# project_konovalov_motor_driver.net
KiCad netlist of a schematic drawn in Altium Designer
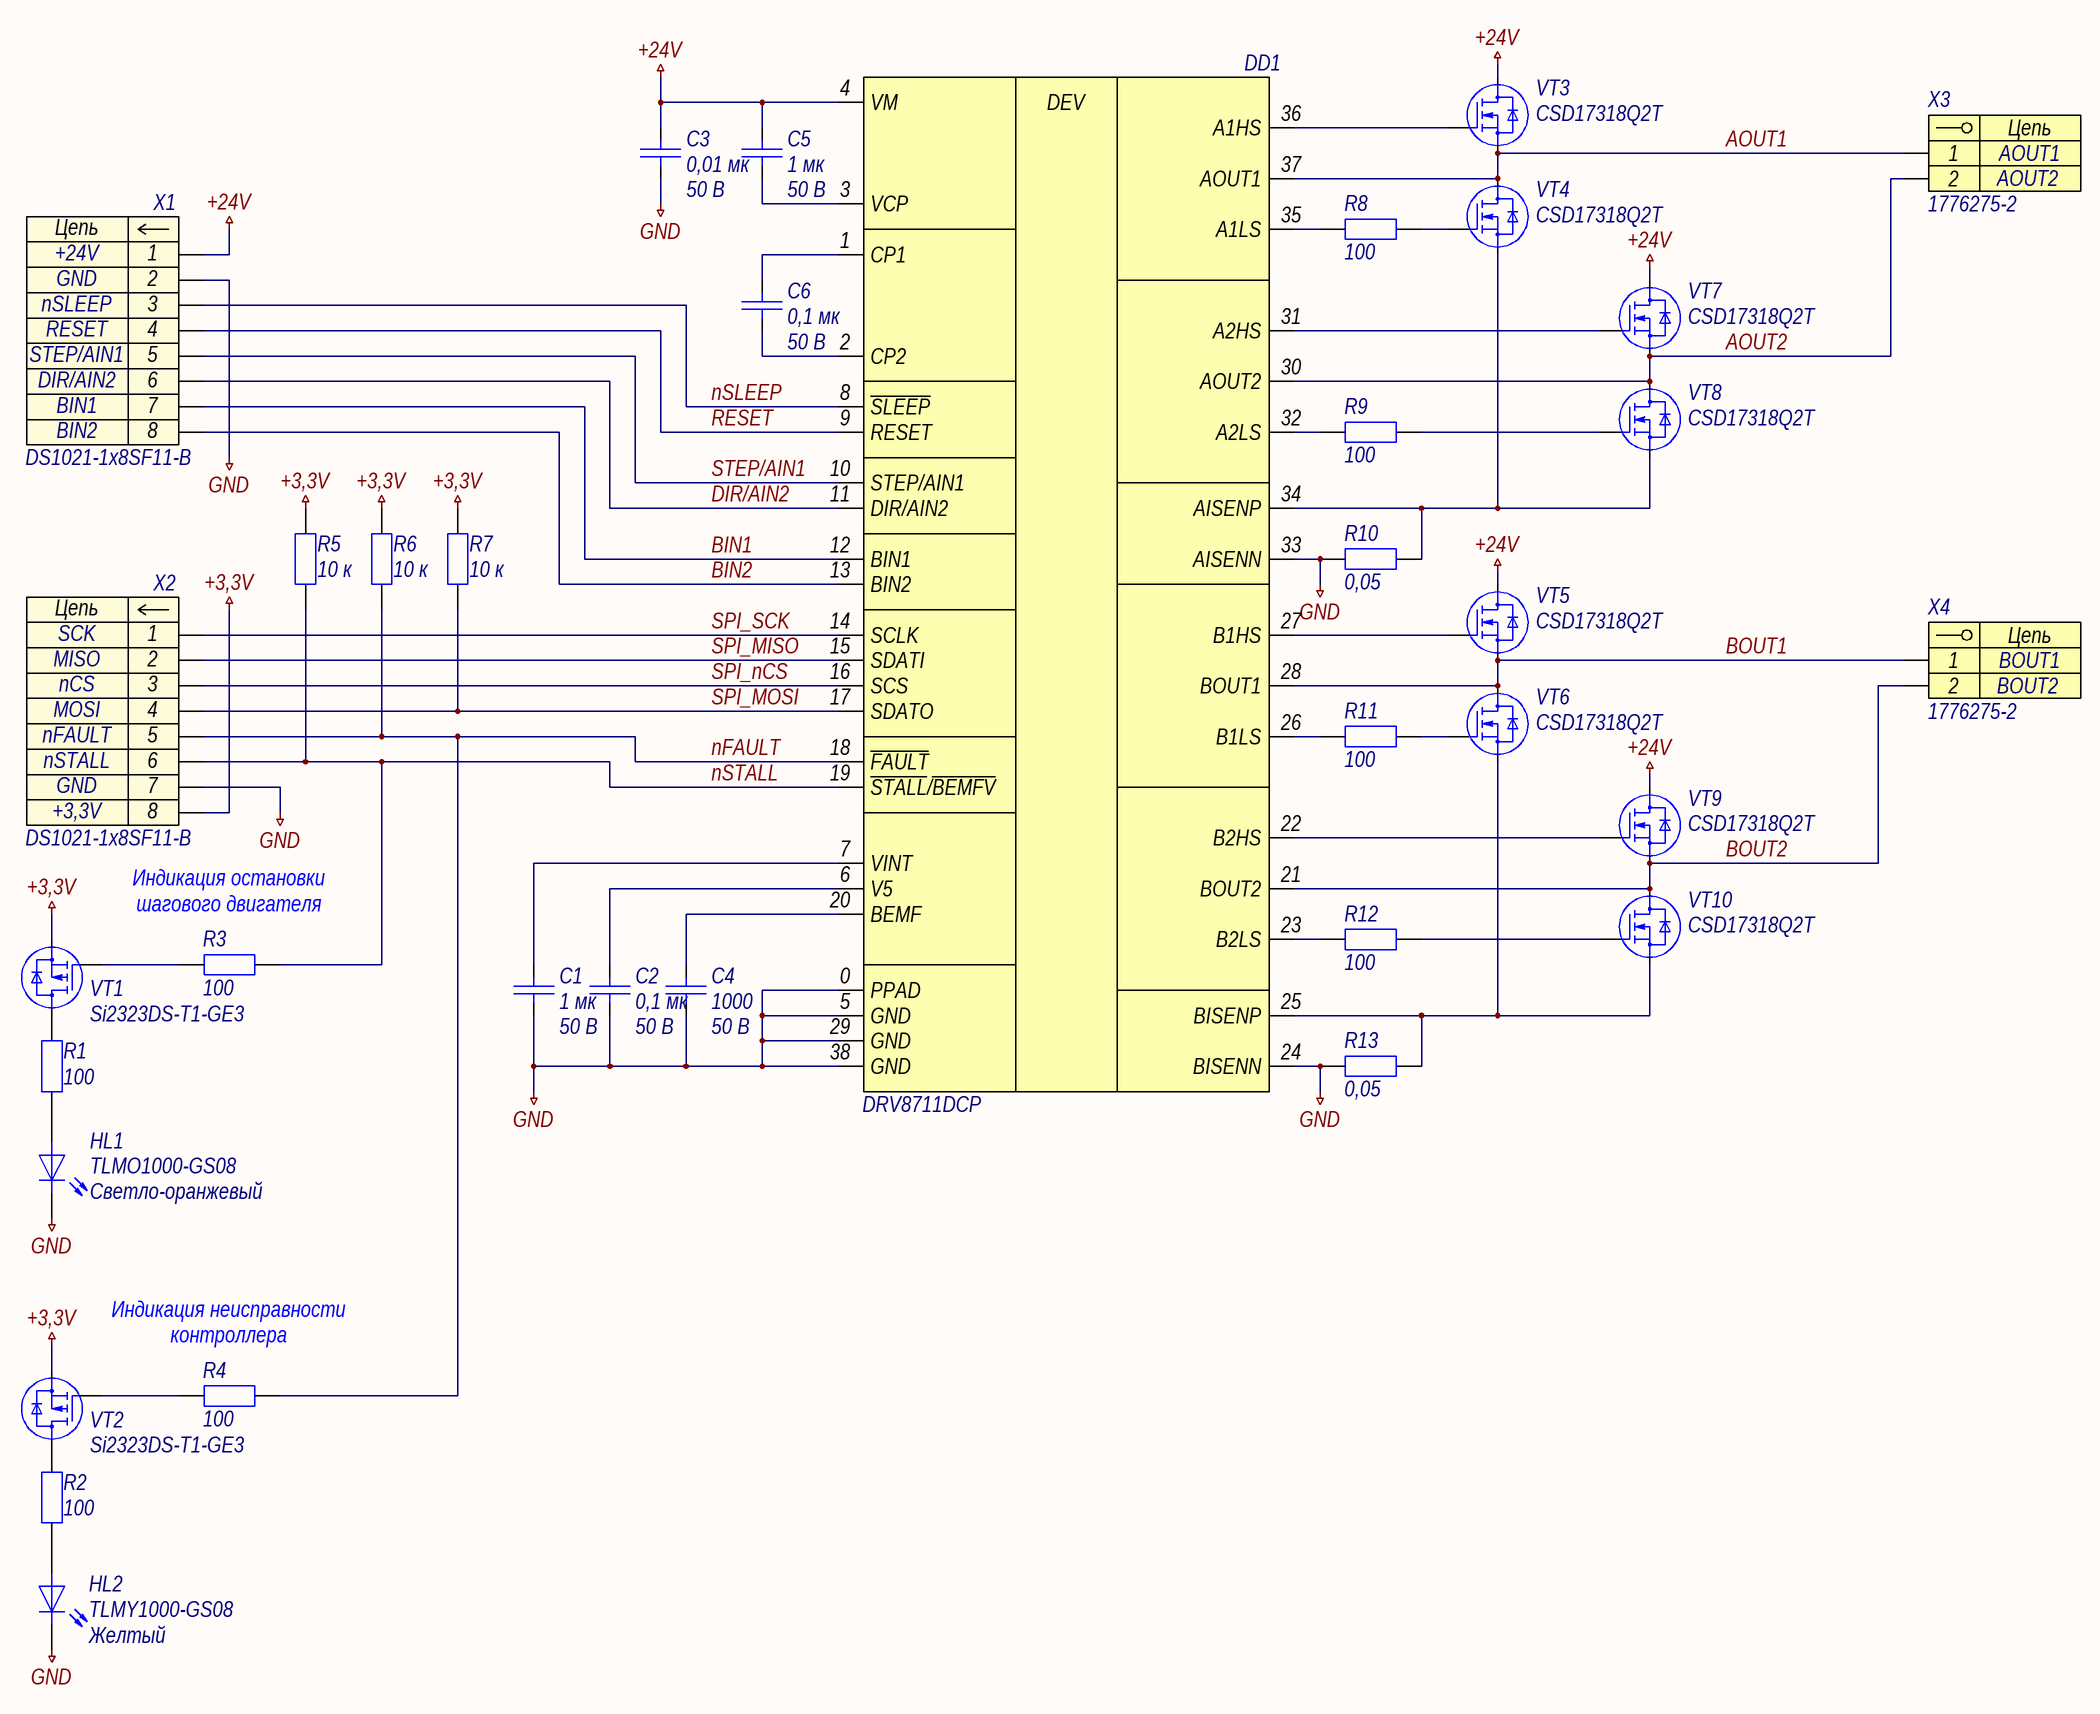
[diagram p0: project_konovalov_motor_driver.SchDoc]

(export (version "E")
  (design (tool "Eeschema 10.0.6"))
  (components
    (comp (ref "C1")
      (value "1 мк")
      (footprint "C0603")
      (description "=Описание")
      (fields (field (name "НАПРЯЖЕНИЕ") "50 В"))
      (libsource (lib "Database_Students") (part "CAPACITOR-NONPOLAR"))
    )
    (comp (ref "C2")
      (value "0,1 мк")
      (footprint "C0603")
      (description "=Описание")
      (fields (field (name "НАПРЯЖЕНИЕ") "50 В"))
      (libsource (lib "Database_Students") (part "CAPACITOR-NONPOLAR"))
    )
    (comp (ref "C3")
      (value "0,01 мк")
      (footprint "C0603")
      (description "=Описание")
      (fields (field (name "НАПРЯЖЕНИЕ") "50 В"))
      (libsource (lib "Database_Students") (part "CAPACITOR-NONPOLAR"))
    )
    (comp (ref "C4")
      (value "1000")
      (footprint "C0603")
      (description "=Описание")
      (fields (field (name "НАПРЯЖЕНИЕ") "50 В"))
      (libsource (lib "Database_Students") (part "CAPACITOR-NONPOLAR"))
    )
    (comp (ref "C5")
      (value "1 мк")
      (footprint "C0603")
      (description "=Описание")
      (fields (field (name "НАПРЯЖЕНИЕ") "50 В"))
      (libsource (lib "Database_Students") (part "CAPACITOR-NONPOLAR"))
    )
    (comp (ref "C6")
      (value "0,1 мк")
      (footprint "C0603")
      (description "=Описание")
      (fields (field (name "НАПРЯЖЕНИЕ") "50 В"))
      (libsource (lib "Database_Students") (part "CAPACITOR-NONPOLAR"))
    )
    (comp (ref "DD1")
      (value "DRV8711DCP")
      (footprint "HTSSOP-38-P50-470X290X120-L63X22-T470X290")
      (description "=Описание")
      (libsource (lib "Database_Students") (part "DRV8711DCP"))
    )
    (comp (ref "HL1")
      (value "TLMO1000-GS08")
      (footprint "HL0603")
      (description "=Описание")
      (fields (field (name "ЦВЕТ") "Светло-оранжевый"))
      (libsource (lib "Database_Students") (part "LED-COMMON"))
    )
    (comp (ref "HL2")
      (value "TLMY1000-GS08")
      (footprint "HL0603")
      (description "=Описание")
      (fields (field (name "ЦВЕТ") "Желтый"))
      (libsource (lib "Database_Students") (part "LED-COMMON"))
    )
    (comp (ref "R1")
      (value "100")
      (footprint "R0603")
      (description "=Описание")
      (libsource (lib "Database_Students") (part "RESISTOR-COMMON"))
    )
    (comp (ref "R2")
      (value "100")
      (footprint "R0603")
      (description "=Описание")
      (libsource (lib "Database_Students") (part "RESISTOR-COMMON"))
    )
    (comp (ref "R3")
      (value "100")
      (footprint "R0603")
      (description "=Описание")
      (libsource (lib "Database_Students") (part "RESISTOR-COMMON"))
    )
    (comp (ref "R4")
      (value "100")
      (footprint "R0603")
      (description "=Описание")
      (libsource (lib "Database_Students") (part "RESISTOR-COMMON"))
    )
    (comp (ref "R5")
      (value "10 к")
      (footprint "R0603")
      (description "=Описание")
      (libsource (lib "Database_Students") (part "RESISTOR-COMMON"))
    )
    (comp (ref "R6")
      (value "10 к")
      (footprint "R0603")
      (description "=Описание")
      (libsource (lib "Database_Students") (part "RESISTOR-COMMON"))
    )
    (comp (ref "R7")
      (value "10 к")
      (footprint "R0603")
      (description "=Описание")
      (libsource (lib "Database_Students") (part "RESISTOR-COMMON"))
    )
    (comp (ref "R8")
      (value "100")
      (footprint "R0603")
      (description "=Описание")
      (libsource (lib "Database_Students") (part "RESISTOR-COMMON"))
    )
    (comp (ref "R9")
      (value "100")
      (footprint "R0603")
      (description "=Описание")
      (libsource (lib "Database_Students") (part "RESISTOR-COMMON"))
    )
    (comp (ref "R10")
      (value "0,05")
      (footprint "R0603")
      (description "=Описание")
      (libsource (lib "Database_Students") (part "RESISTOR-COMMON"))
    )
    (comp (ref "R11")
      (value "100")
      (footprint "R0603")
      (description "=Описание")
      (libsource (lib "Database_Students") (part "RESISTOR-COMMON"))
    )
    (comp (ref "R12")
      (value "100")
      (footprint "R0603")
      (description "=Описание")
      (libsource (lib "Database_Students") (part "RESISTOR-COMMON"))
    )
    (comp (ref "R13")
      (value "0,05")
      (footprint "R0603")
      (description "=Описание")
      (libsource (lib "Database_Students") (part "RESISTOR-COMMON"))
    )
    (comp (ref "VT1")
      (value "Si2323DS-T1-GE3")
      (footprint "SOT-23-3-P95-292X237X112")
      (description "=Описание")
      (libsource (lib "Database_Students") (part "MOSFET-P-DIODE"))
    )
    (comp (ref "VT2")
      (value "Si2323DS-T1-GE3")
      (footprint "SOT-23-3-P95-292X237X112")
      (description "=Описание")
      (libsource (lib "Database_Students") (part "MOSFET-P-DIODE"))
    )
    (comp (ref "VT3")
      (value "CSD17318Q2T")
      (footprint "WSON-6-P65-200X200X80")
      (description "=Описание")
      (libsource (lib "Database_Students") (part "MOSFET-N-DIODE"))
    )
    (comp (ref "VT4")
      (value "CSD17318Q2T")
      (footprint "WSON-6-P65-200X200X80")
      (description "=Описание")
      (libsource (lib "Database_Students") (part "MOSFET-N-DIODE"))
    )
    (comp (ref "VT5")
      (value "CSD17318Q2T")
      (footprint "WSON-6-P65-200X200X80")
      (description "=Описание")
      (libsource (lib "Database_Students") (part "MOSFET-N-DIODE"))
    )
    (comp (ref "VT6")
      (value "CSD17318Q2T")
      (footprint "WSON-6-P65-200X200X80")
      (description "=Описание")
      (libsource (lib "Database_Students") (part "MOSFET-N-DIODE"))
    )
    (comp (ref "VT7")
      (value "CSD17318Q2T")
      (footprint "WSON-6-P65-200X200X80")
      (description "=Описание")
      (libsource (lib "Database_Students") (part "MOSFET-N-DIODE"))
    )
    (comp (ref "VT8")
      (value "CSD17318Q2T")
      (footprint "WSON-6-P65-200X200X80")
      (description "=Описание")
      (libsource (lib "Database_Students") (part "MOSFET-N-DIODE"))
    )
    (comp (ref "VT9")
      (value "CSD17318Q2T")
      (footprint "WSON-6-P65-200X200X80")
      (description "=Описание")
      (libsource (lib "Database_Students") (part "MOSFET-N-DIODE"))
    )
    (comp (ref "VT10")
      (value "CSD17318Q2T")
      (footprint "WSON-6-P65-200X200X80")
      (description "=Описание")
      (libsource (lib "Database_Students") (part "MOSFET-N-DIODE"))
    )
    (comp (ref "X1")
      (value "DS1021-1x8SF11-B")
      (footprint "DS1021-1X8SF11-B")
      (description "=Описание")
      (libsource (lib "Database_Students") (part "HEADER-8-PLG"))
    )
    (comp (ref "X2")
      (value "DS1021-1x8SF11-B")
      (footprint "DS1021-1X8SF11-B")
      (description "=Описание")
      (libsource (lib "Database_Students") (part "HEADER-8-PLG"))
    )
    (comp (ref "X3")
      (value "1776275-2")
      (footprint "1776275-2")
      (description "=Описание")
      (libsource (lib "Database_Students") (part "HEADER-2-TRM"))
    )
    (comp (ref "X4")
      (value "1776275-2")
      (footprint "1776275-2")
      (description "=Описание")
      (libsource (lib "Database_Students") (part "HEADER-2-TRM"))
    )
  )
  (nets
    (net (code "1") (name "+3,3V") (class "Default")
      (node (ref "R5") (pin "2") (pinfunction "2_2") (pintype "passive"))
      (node (ref "R6") (pin "2") (pinfunction "2_2") (pintype "passive"))
      (node (ref "R7") (pin "2") (pinfunction "2_2") (pintype "passive"))
      (node (ref "VT1") (pin "S") (pinfunction "S_S") (pintype "passive"))
      (node (ref "VT2") (pin "S") (pinfunction "S_S") (pintype "passive"))
      (node (ref "X2") (pin "8") (pinfunction "8_8") (pintype "passive"))
    )
    (net (code "2") (name "+24V") (class "Default")
      (node (ref "C3") (pin "1") (pinfunction "1_1") (pintype "passive"))
      (node (ref "C5") (pin "1") (pinfunction "1_1") (pintype "passive"))
      (node (ref "DD1") (pin "4") (pinfunction "VM_4") (pintype "passive"))
      (node (ref "VT3") (pin "D") (pinfunction "D_D") (pintype "passive"))
      (node (ref "VT5") (pin "D") (pinfunction "D_D") (pintype "passive"))
      (node (ref "VT7") (pin "D") (pinfunction "D_D") (pintype "passive"))
      (node (ref "VT9") (pin "D") (pinfunction "D_D") (pintype "passive"))
      (node (ref "X1") (pin "1") (pinfunction "1_1") (pintype "passive"))
    )
    (net (code "3") (name "/AOUT1") (class "Default")
      (node (ref "DD1") (pin "37") (pinfunction "AOUT1_37") (pintype "passive"))
      (node (ref "VT3") (pin "S") (pinfunction "S_S") (pintype "passive"))
      (node (ref "VT4") (pin "D") (pinfunction "D_D") (pintype "passive"))
      (node (ref "X3") (pin "1") (pinfunction "1_1") (pintype "passive"))
    )
    (net (code "4") (name "/AOUT2") (class "Default")
      (node (ref "DD1") (pin "30") (pinfunction "AOUT2_30") (pintype "passive"))
      (node (ref "VT7") (pin "S") (pinfunction "S_S") (pintype "passive"))
      (node (ref "VT8") (pin "D") (pinfunction "D_D") (pintype "passive"))
      (node (ref "X3") (pin "2") (pinfunction "2_2") (pintype "passive"))
    )
    (net (code "5") (name "/BIN1") (class "Default")
      (node (ref "DD1") (pin "12") (pinfunction "BIN1_12") (pintype "passive"))
      (node (ref "X1") (pin "7") (pinfunction "7_7") (pintype "passive"))
    )
    (net (code "6") (name "/BIN2") (class "Default")
      (node (ref "DD1") (pin "13") (pinfunction "BIN2_13") (pintype "passive"))
      (node (ref "X1") (pin "8") (pinfunction "8_8") (pintype "passive"))
    )
    (net (code "7") (name "/BOUT1") (class "Default")
      (node (ref "DD1") (pin "28") (pinfunction "BOUT1_28") (pintype "passive"))
      (node (ref "VT5") (pin "S") (pinfunction "S_S") (pintype "passive"))
      (node (ref "VT6") (pin "D") (pinfunction "D_D") (pintype "passive"))
      (node (ref "X4") (pin "1") (pinfunction "1_1") (pintype "passive"))
    )
    (net (code "8") (name "/BOUT2") (class "Default")
      (node (ref "DD1") (pin "21") (pinfunction "BOUT2_21") (pintype "passive"))
      (node (ref "VT10") (pin "D") (pinfunction "D_D") (pintype "passive"))
      (node (ref "VT9") (pin "S") (pinfunction "S_S") (pintype "passive"))
      (node (ref "X4") (pin "2") (pinfunction "2_2") (pintype "passive"))
    )
    (net (code "9") (name "/DIR{slash}AIN2") (class "Default")
      (node (ref "DD1") (pin "11") (pinfunction "DIR/AIN2_11") (pintype "passive"))
      (node (ref "X1") (pin "6") (pinfunction "6_6") (pintype "passive"))
    )
    (net (code "10") (name "/RESET") (class "Default")
      (node (ref "DD1") (pin "9") (pinfunction "RESET_9") (pintype "passive"))
      (node (ref "X1") (pin "4") (pinfunction "4_4") (pintype "passive"))
    )
    (net (code "11") (name "/SPI_MISO") (class "Default")
      (node (ref "DD1") (pin "15") (pinfunction "SDATI_15") (pintype "passive"))
      (node (ref "X2") (pin "2") (pinfunction "2_2") (pintype "passive"))
    )
    (net (code "12") (name "/SPI_MOSI") (class "Default")
      (node (ref "DD1") (pin "17") (pinfunction "SDATO_17") (pintype "passive"))
      (node (ref "R7") (pin "1") (pinfunction "1_1") (pintype "passive"))
      (node (ref "X2") (pin "4") (pinfunction "4_4") (pintype "passive"))
    )
    (net (code "13") (name "/SPI_SCK") (class "Default")
      (node (ref "DD1") (pin "14") (pinfunction "SCLK_14") (pintype "passive"))
      (node (ref "X2") (pin "1") (pinfunction "1_1") (pintype "passive"))
    )
    (net (code "14") (name "/SPI_nCS") (class "Default")
      (node (ref "DD1") (pin "16") (pinfunction "SCS_16") (pintype "passive"))
      (node (ref "X2") (pin "3") (pinfunction "3_3") (pintype "passive"))
    )
    (net (code "15") (name "/STEP{slash}AIN1") (class "Default")
      (node (ref "DD1") (pin "10") (pinfunction "STEP/AIN1_10") (pintype "passive"))
      (node (ref "X1") (pin "5") (pinfunction "5_5") (pintype "passive"))
    )
    (net (code "16") (name "/nFAULT") (class "Default")
      (node (ref "DD1") (pin "18") (pinfunction "~{FAULT}_18") (pintype "passive"))
      (node (ref "R4") (pin "2") (pinfunction "2_2") (pintype "passive"))
      (node (ref "R6") (pin "1") (pinfunction "1_1") (pintype "passive"))
      (node (ref "X2") (pin "5") (pinfunction "5_5") (pintype "passive"))
    )
    (net (code "17") (name "/nSLEEP") (class "Default")
      (node (ref "DD1") (pin "8") (pinfunction "~{SLEEP}_8") (pintype "passive"))
      (node (ref "X1") (pin "3") (pinfunction "3_3") (pintype "passive"))
    )
    (net (code "18") (name "/nSTALL") (class "Default")
      (node (ref "DD1") (pin "19") (pinfunction "~{STALL}/~{BEMFV}_19") (pintype "passive"))
      (node (ref "R3") (pin "2") (pinfunction "2_2") (pintype "passive"))
      (node (ref "R5") (pin "1") (pinfunction "1_1") (pintype "passive"))
      (node (ref "X2") (pin "6") (pinfunction "6_6") (pintype "passive"))
    )
    (net (code "19") (name "GND") (class "Default")
      (node (ref "C1") (pin "2") (pinfunction "2_2") (pintype "passive"))
      (node (ref "C2") (pin "2") (pinfunction "2_2") (pintype "passive"))
      (node (ref "C3") (pin "2") (pinfunction "2_2") (pintype "passive"))
      (node (ref "C4") (pin "2") (pinfunction "2_2") (pintype "passive"))
      (node (ref "DD1") (pin "0") (pinfunction "PPAD_0") (pintype "passive"))
      (node (ref "DD1") (pin "24") (pinfunction "BISENN_24") (pintype "passive"))
      (node (ref "DD1") (pin "29") (pinfunction "GND_29") (pintype "passive"))
      (node (ref "DD1") (pin "33") (pinfunction "AISENN_33") (pintype "passive"))
      (node (ref "DD1") (pin "38") (pinfunction "GND_38") (pintype "passive"))
      (node (ref "DD1") (pin "5") (pinfunction "GND_5") (pintype "passive"))
      (node (ref "HL1") (pin "1") (pinfunction "1_1") (pintype "passive"))
      (node (ref "HL2") (pin "1") (pinfunction "1_1") (pintype "passive"))
      (node (ref "R10") (pin "1") (pinfunction "1_1") (pintype "passive"))
      (node (ref "R13") (pin "1") (pinfunction "1_1") (pintype "passive"))
      (node (ref "X1") (pin "2") (pinfunction "2_2") (pintype "passive"))
      (node (ref "X2") (pin "7") (pinfunction "7_7") (pintype "passive"))
    )
    (net (code "20") (name "Net-(DD1-A1HS)") (class "Default")
      (node (ref "DD1") (pin "36") (pinfunction "A1HS_36") (pintype "passive"))
      (node (ref "VT3") (pin "G") (pinfunction "G_G") (pintype "passive"))
    )
    (net (code "21") (name "Net-(DD1-A1LS)") (class "Default")
      (node (ref "DD1") (pin "35") (pinfunction "A1LS_35") (pintype "passive"))
      (node (ref "R8") (pin "1") (pinfunction "1_1") (pintype "passive"))
    )
    (net (code "22") (name "Net-(DD1-A2HS)") (class "Default")
      (node (ref "DD1") (pin "31") (pinfunction "A2HS_31") (pintype "passive"))
      (node (ref "VT7") (pin "G") (pinfunction "G_G") (pintype "passive"))
    )
    (net (code "23") (name "Net-(DD1-A2LS)") (class "Default")
      (node (ref "DD1") (pin "32") (pinfunction "A2LS_32") (pintype "passive"))
      (node (ref "R9") (pin "1") (pinfunction "1_1") (pintype "passive"))
    )
    (net (code "24") (name "Net-(DD1-AISENP)") (class "Default")
      (node (ref "DD1") (pin "34") (pinfunction "AISENP_34") (pintype "passive"))
      (node (ref "R10") (pin "2") (pinfunction "2_2") (pintype "passive"))
      (node (ref "VT4") (pin "S") (pinfunction "S_S") (pintype "passive"))
      (node (ref "VT8") (pin "S") (pinfunction "S_S") (pintype "passive"))
    )
    (net (code "25") (name "Net-(DD1-B1HS)") (class "Default")
      (node (ref "DD1") (pin "27") (pinfunction "B1HS_27") (pintype "passive"))
      (node (ref "VT5") (pin "G") (pinfunction "G_G") (pintype "passive"))
    )
    (net (code "26") (name "Net-(DD1-B1LS)") (class "Default")
      (node (ref "DD1") (pin "26") (pinfunction "B1LS_26") (pintype "passive"))
      (node (ref "R11") (pin "1") (pinfunction "1_1") (pintype "passive"))
    )
    (net (code "27") (name "Net-(DD1-B2HS)") (class "Default")
      (node (ref "DD1") (pin "22") (pinfunction "B2HS_22") (pintype "passive"))
      (node (ref "VT9") (pin "G") (pinfunction "G_G") (pintype "passive"))
    )
    (net (code "28") (name "Net-(DD1-B2LS)") (class "Default")
      (node (ref "DD1") (pin "23") (pinfunction "B2LS_23") (pintype "passive"))
      (node (ref "R12") (pin "1") (pinfunction "1_1") (pintype "passive"))
    )
    (net (code "29") (name "Net-(DD1-BEMF)") (class "Default")
      (node (ref "C4") (pin "1") (pinfunction "1_1") (pintype "passive"))
      (node (ref "DD1") (pin "20") (pinfunction "BEMF_20") (pintype "passive"))
    )
    (net (code "30") (name "Net-(DD1-BISENP)") (class "Default")
      (node (ref "DD1") (pin "25") (pinfunction "BISENP_25") (pintype "passive"))
      (node (ref "R13") (pin "2") (pinfunction "2_2") (pintype "passive"))
      (node (ref "VT10") (pin "S") (pinfunction "S_S") (pintype "passive"))
      (node (ref "VT6") (pin "S") (pinfunction "S_S") (pintype "passive"))
    )
    (net (code "31") (name "Net-(DD1-CP1)") (class "Default")
      (node (ref "C6") (pin "1") (pinfunction "1_1") (pintype "passive"))
      (node (ref "DD1") (pin "1") (pinfunction "CP1_1") (pintype "passive"))
    )
    (net (code "32") (name "Net-(DD1-CP2)") (class "Default")
      (node (ref "C6") (pin "2") (pinfunction "2_2") (pintype "passive"))
      (node (ref "DD1") (pin "2") (pinfunction "CP2_2") (pintype "passive"))
    )
    (net (code "33") (name "Net-(DD1-V5)") (class "Default")
      (node (ref "C2") (pin "1") (pinfunction "1_1") (pintype "passive"))
      (node (ref "DD1") (pin "6") (pinfunction "V5_6") (pintype "passive"))
    )
    (net (code "34") (name "Net-(DD1-VCP)") (class "Default")
      (node (ref "C5") (pin "2") (pinfunction "2_2") (pintype "passive"))
      (node (ref "DD1") (pin "3") (pinfunction "VCP_3") (pintype "passive"))
    )
    (net (code "35") (name "Net-(DD1-VINT)") (class "Default")
      (node (ref "C1") (pin "1") (pinfunction "1_1") (pintype "passive"))
      (node (ref "DD1") (pin "7") (pinfunction "VINT_7") (pintype "passive"))
    )
    (net (code "36") (name "Net-(HL1-Pad2)") (class "Default")
      (node (ref "HL1") (pin "2") (pinfunction "2_2") (pintype "passive"))
      (node (ref "R1") (pin "1") (pinfunction "1_1") (pintype "passive"))
    )
    (net (code "37") (name "Net-(HL2-Pad2)") (class "Default")
      (node (ref "HL2") (pin "2") (pinfunction "2_2") (pintype "passive"))
      (node (ref "R2") (pin "1") (pinfunction "1_1") (pintype "passive"))
    )
    (net (code "38") (name "Net-(R1-Pad2)") (class "Default")
      (node (ref "R1") (pin "2") (pinfunction "2_2") (pintype "passive"))
      (node (ref "VT1") (pin "D") (pinfunction "D_D") (pintype "passive"))
    )
    (net (code "39") (name "Net-(R2-Pad2)") (class "Default")
      (node (ref "R2") (pin "2") (pinfunction "2_2") (pintype "passive"))
      (node (ref "VT2") (pin "D") (pinfunction "D_D") (pintype "passive"))
    )
    (net (code "40") (name "Net-(R3-Pad1)") (class "Default")
      (node (ref "R3") (pin "1") (pinfunction "1_1") (pintype "passive"))
      (node (ref "VT1") (pin "G") (pinfunction "G_G") (pintype "passive"))
    )
    (net (code "41") (name "Net-(R4-Pad1)") (class "Default")
      (node (ref "R4") (pin "1") (pinfunction "1_1") (pintype "passive"))
      (node (ref "VT2") (pin "G") (pinfunction "G_G") (pintype "passive"))
    )
    (net (code "42") (name "Net-(R8-Pad2)") (class "Default")
      (node (ref "R8") (pin "2") (pinfunction "2_2") (pintype "passive"))
      (node (ref "VT4") (pin "G") (pinfunction "G_G") (pintype "passive"))
    )
    (net (code "43") (name "Net-(R9-Pad2)") (class "Default")
      (node (ref "R9") (pin "2") (pinfunction "2_2") (pintype "passive"))
      (node (ref "VT8") (pin "G") (pinfunction "G_G") (pintype "passive"))
    )
    (net (code "44") (name "Net-(R11-Pad2)") (class "Default")
      (node (ref "R11") (pin "2") (pinfunction "2_2") (pintype "passive"))
      (node (ref "VT6") (pin "G") (pinfunction "G_G") (pintype "passive"))
    )
    (net (code "45") (name "Net-(R12-Pad2)") (class "Default")
      (node (ref "R12") (pin "2") (pinfunction "2_2") (pintype "passive"))
      (node (ref "VT10") (pin "G") (pinfunction "G_G") (pintype "passive"))
    )
  )
)
